# gba-zero.net
KiCad netlist of a schematic drawn in EAGLE
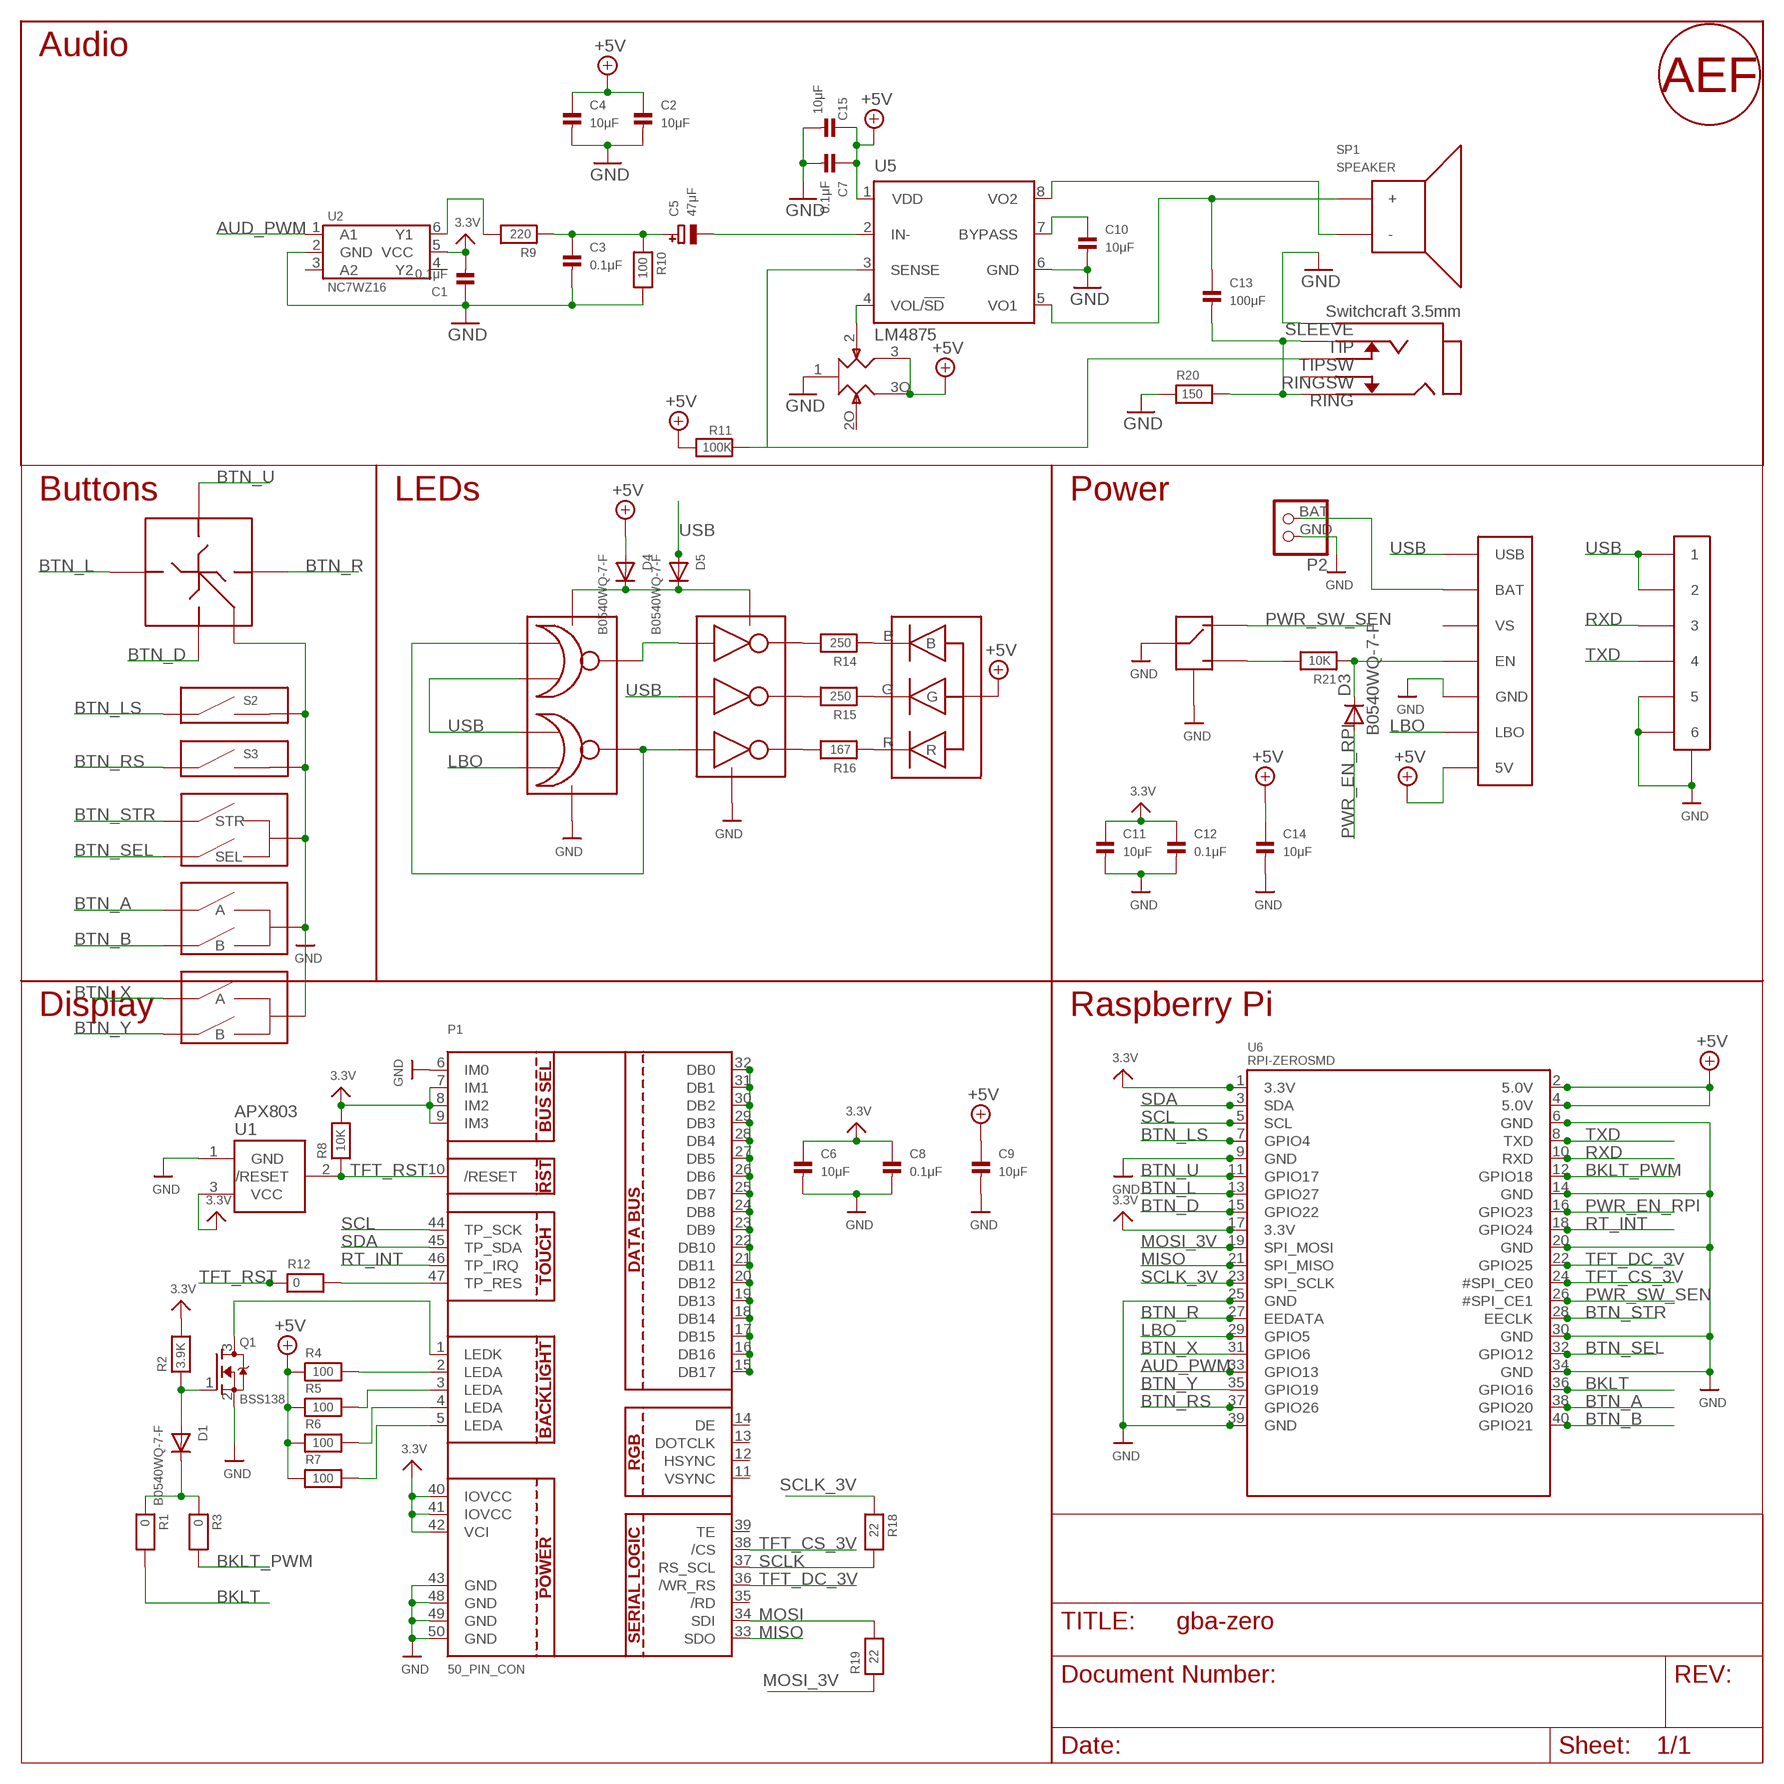
[diagram p0: schematic, sheet 1]

(export (version "E")
  (design (tool "Eeschema 10.0.6"))
  (components
    (comp (ref "C1")
      (value "0.1μF")
      (footprint "eagle-import:0603")
      (libsource (lib "eagle-import") (part "CAP_CERAMIC0603"))
    )
    (comp (ref "C2")
      (value "10μF")
      (footprint "eagle-import:0603")
      (libsource (lib "eagle-import") (part "CAP_CERAMIC0603"))
    )
    (comp (ref "C3")
      (value "0.1μF")
      (footprint "eagle-import:0603")
      (libsource (lib "eagle-import") (part "CAP_CERAMIC0603"))
    )
    (comp (ref "C4")
      (value "10μF")
      (footprint "eagle-import:0603")
      (libsource (lib "eagle-import") (part "CAP_CERAMIC0603"))
    )
    (comp (ref "C5")
      (value "47μF")
      (footprint "eagle-import:EIA6032-28_C-R")
      (libsource (lib "eagle-import") (part "CAP_TANTALUMC/6032_REFLOW"))
    )
    (comp (ref "C6")
      (value "10μF")
      (footprint "eagle-import:0603")
      (libsource (lib "eagle-import") (part "CAP_CERAMIC0603"))
    )
    (comp (ref "C7")
      (value "0.1μF")
      (footprint "eagle-import:0603")
      (libsource (lib "eagle-import") (part "CAP_CERAMIC0603"))
    )
    (comp (ref "C8")
      (value "0.1μF")
      (footprint "eagle-import:0603")
      (libsource (lib "eagle-import") (part "CAP_CERAMIC0603"))
    )
    (comp (ref "C9")
      (value "10μF")
      (footprint "eagle-import:0603")
      (libsource (lib "eagle-import") (part "CAP_CERAMIC0603"))
    )
    (comp (ref "C10")
      (value "10μF")
      (footprint "eagle-import:0603")
      (libsource (lib "eagle-import") (part "CAP_CERAMIC0603"))
    )
    (comp (ref "C11")
      (value "10μF")
      (footprint "eagle-import:0603")
      (libsource (lib "eagle-import") (part "CAP_CERAMIC0603"))
    )
    (comp (ref "C12")
      (value "0.1μF")
      (footprint "eagle-import:0603")
      (libsource (lib "eagle-import") (part "CAP_CERAMIC0603"))
    )
    (comp (ref "C13")
      (value "100μF")
      (footprint "eagle-import:1206")
      (libsource (lib "eagle-import") (part "CAP_CERAMIC1206"))
    )
    (comp (ref "C14")
      (value "10μF")
      (footprint "eagle-import:0603")
      (libsource (lib "eagle-import") (part "CAP_CERAMIC0603"))
    )
    (comp (ref "C15")
      (value "10μF")
      (footprint "eagle-import:0603")
      (libsource (lib "eagle-import") (part "CAP_CERAMIC0603"))
    )
    (comp (ref "D1")
      (value "B0540WQ-7-F")
      (footprint "eagle-import:SOD-123")
      (libsource (lib "eagle-import") (part "DIODESOD-123"))
    )
    (comp (ref "D2")
      (value "LTST-C19HE1WT")
      (footprint "eagle-import:WL-SBCW-0606")
      (libsource (lib "eagle-import") (part "LTST-C19HE1WT"))
    )
    (comp (ref "D3")
      (value "B0540WQ-7-F")
      (footprint "eagle-import:SOD-123")
      (libsource (lib "eagle-import") (part "DIODESOD-123"))
    )
    (comp (ref "D4")
      (value "B0540WQ-7-F")
      (footprint "eagle-import:SOD-123")
      (libsource (lib "eagle-import") (part "DIODESOD-123"))
    )
    (comp (ref "D5")
      (value "B0540WQ-7-F")
      (footprint "eagle-import:SOD-123")
      (libsource (lib "eagle-import") (part "DIODESOD-123"))
    )
    (comp (ref "J1")
      (value "SWTCHCRFT_3.5JACK5-JACK-SMD")
      (footprint "eagle-import:4-JACK-SMD")
      (libsource (lib "eagle-import") (part "SWTCHCRFT_3.5JACK5-JACK-SMD"))
    )
    (comp (ref "P1")
      (value "50_PIN_CON")
      (footprint "eagle-import:FPC-50-CON")
      (libsource (lib "eagle-import") (part "DISP_LCD_CTP28"))
    )
    (comp (ref "P2")
      (value "JST_2PIN")
      (footprint "eagle-import:JSTPH2")
      (libsource (lib "eagle-import") (part "JST_2PIN"))
    )
    (comp (ref "P3")
      (value "LINK_CONNECTOR")
      (footprint "eagle-import:LINK_CONNECTOR")
      (libsource (lib "eagle-import") (part "LINK_CONNECTOR"))
    )
    (comp (ref "Q1")
      (value "BSS138")
      (footprint "eagle-import:SOT23-WIDE")
      (libsource (lib "eagle-import") (part "MOSFET-NWIDE"))
    )
    (comp (ref "R1")
      (value "0")
      (footprint "eagle-import:0603")
      (libsource (lib "eagle-import") (part "RESISTOR0603"))
    )
    (comp (ref "R2")
      (value "3.9K")
      (footprint "eagle-import:0603")
      (libsource (lib "eagle-import") (part "RESISTOR0603"))
    )
    (comp (ref "R3")
      (value "0")
      (footprint "eagle-import:0603")
      (libsource (lib "eagle-import") (part "RESISTOR0603"))
    )
    (comp (ref "R4")
      (value "100")
      (footprint "eagle-import:0603")
      (libsource (lib "eagle-import") (part "RESISTOR0603"))
    )
    (comp (ref "R5")
      (value "100")
      (footprint "eagle-import:0603")
      (libsource (lib "eagle-import") (part "RESISTOR0603"))
    )
    (comp (ref "R6")
      (value "100")
      (footprint "eagle-import:0603")
      (libsource (lib "eagle-import") (part "RESISTOR0603"))
    )
    (comp (ref "R7")
      (value "100")
      (footprint "eagle-import:0603")
      (libsource (lib "eagle-import") (part "RESISTOR0603"))
    )
    (comp (ref "R8")
      (value "10K")
      (footprint "eagle-import:0603")
      (libsource (lib "eagle-import") (part "RESISTOR0603"))
    )
    (comp (ref "R9")
      (value "220")
      (footprint "eagle-import:0603")
      (libsource (lib "eagle-import") (part "RESISTOR0603"))
    )
    (comp (ref "R10")
      (value "100")
      (footprint "eagle-import:0603")
      (libsource (lib "eagle-import") (part "RESISTOR0603"))
    )
    (comp (ref "R11")
      (value "100K")
      (footprint "eagle-import:0603")
      (libsource (lib "eagle-import") (part "RESISTOR0603"))
    )
    (comp (ref "R12")
      (value "0")
      (footprint "eagle-import:0603")
      (libsource (lib "eagle-import") (part "RESISTOR0603"))
    )
    (comp (ref "R14")
      (value "250")
      (footprint "eagle-import:0603")
      (libsource (lib "eagle-import") (part "RESISTOR0603"))
    )
    (comp (ref "R15")
      (value "250")
      (footprint "eagle-import:0603")
      (libsource (lib "eagle-import") (part "RESISTOR0603"))
    )
    (comp (ref "R16")
      (value "167")
      (footprint "eagle-import:0603")
      (libsource (lib "eagle-import") (part "RESISTOR0603"))
    )
    (comp (ref "R17")
      (value "10K")
      (footprint "eagle-import:RK10J12E0A0A")
      (libsource (lib "eagle-import") (part "RK10J12E0A0A"))
    )
    (comp (ref "R18")
      (value "22")
      (footprint "eagle-import:0603")
      (libsource (lib "eagle-import") (part "RESISTOR0603"))
    )
    (comp (ref "R19")
      (value "22")
      (footprint "eagle-import:0603")
      (libsource (lib "eagle-import") (part "RESISTOR0603"))
    )
    (comp (ref "R20")
      (value "150")
      (footprint "eagle-import:0603")
      (libsource (lib "eagle-import") (part "RESISTOR0603"))
    )
    (comp (ref "R21")
      (value "10K")
      (footprint "eagle-import:0603")
      (libsource (lib "eagle-import") (part "RESISTOR0603"))
    )
    (comp (ref "S1")
      (value "D-PAD")
      (footprint "eagle-import:D-PAD")
      (libsource (lib "eagle-import") (part "D-PAD"))
    )
    (comp (ref "S2")
      (value "SHOULDER_BUTTON")
      (footprint "eagle-import:SHOULDER_BUTTON")
      (libsource (lib "eagle-import") (part "SHOULDER_BUTTON"))
    )
    (comp (ref "S3")
      (value "SHOULDER_BUTTON")
      (footprint "eagle-import:SHOULDER_BUTTON")
      (libsource (lib "eagle-import") (part "SHOULDER_BUTTON"))
    )
    (comp (ref "S4")
      (value "START_SELECT_BUTTON")
      (footprint "eagle-import:START_SELECT_BUTTON")
      (libsource (lib "eagle-import") (part "START_SELECT_BUTTON"))
    )
    (comp (ref "S5")
      (value "AB_BUTTON")
      (footprint "eagle-import:AB_BUTTON")
      (libsource (lib "eagle-import") (part "AB_BUTTON"))
    )
    (comp (ref "S6")
      (value "PWR_SWITCH")
      (footprint "eagle-import:PWR-SWITCH")
      (libsource (lib "eagle-import") (part "PWR_SWITCH"))
    )
    (comp (ref "S7")
      (value "AB_BUTTON")
      (footprint "eagle-import:AB_BUTTON")
      (libsource (lib "eagle-import") (part "gbz master_AB_BUTTON"))
    )
    (comp (ref "SP1")
      (value "SPEAKER")
      (footprint "eagle-import:SPEAKER")
      (libsource (lib "eagle-import") (part "SPEAKER"))
    )
    (comp (ref "U$1")
      (value "SIGNATURE")
      (footprint "eagle-import:SIGNATURE")
      (libsource (lib "eagle-import") (part "SIGNATURE"))
    )
    (comp (ref "U1")
      (value "APX803")
      (footprint "eagle-import:SOT23")
      (libsource (lib "eagle-import") (part "AXP083-SAG"))
    )
    (comp (ref "U2")
      (value "NC7WZ16")
      (footprint "eagle-import:SC-70-6")
      (libsource (lib "eagle-import") (part "NC7WZ16"))
    )
    (comp (ref "U3")
      (value "74LVC2G02")
      (footprint "eagle-import:TSSOP-8")
      (libsource (lib "eagle-import") (part "74LVC2G02"))
    )
    (comp (ref "U4")
      (value "74LVC3G04")
      (footprint "eagle-import:TSSOP-8")
      (libsource (lib "eagle-import") (part "74LVC3G04"))
    )
    (comp (ref "U5")
      (value "LM4875")
      (footprint "eagle-import:SO-8")
      (libsource (lib "eagle-import") (part "LM4875"))
    )
    (comp (ref "U6")
      (value "RPI-ZEROSMD")
      (footprint "eagle-import:RPI-SMD")
      (libsource (lib "eagle-import") (part "RPI-ZEROSMD"))
    )
    (comp (ref "U7")
      (value "POWERBOOST-1000C")
      (footprint "eagle-import:POWERBOOST-1000C")
      (libsource (lib "eagle-import") (part "POWERBOOST-1000C"))
    )
  )
  (nets
    (net (code "1") (name "+5V") (class "Default")
      (node (ref "C14") (pin "1") (pinfunction "P$1_1") (pintype "passive"))
      (node (ref "C15") (pin "1") (pinfunction "P$1_1") (pintype "passive"))
      (node (ref "C2") (pin "1") (pinfunction "P$1_1") (pintype "passive"))
      (node (ref "C4") (pin "1") (pinfunction "P$1_1") (pintype "passive"))
      (node (ref "C7") (pin "1") (pinfunction "P$1_1") (pintype "passive"))
      (node (ref "C9") (pin "1") (pinfunction "P$1_1") (pintype "passive"))
      (node (ref "D2") (pin "VCC") (pinfunction "VCC_VCC") (pintype "bidirectional"))
      (node (ref "D4") (pin "A") (pinfunction "A_A") (pintype "passive"))
      (node (ref "R11") (pin "2") (pinfunction "2_2") (pintype "passive"))
      (node (ref "R17") (pin "3") (pinfunction "3_3") (pintype "bidirectional"))
      (node (ref "R17") (pin "3O") (pinfunction "3O_3O") (pintype "bidirectional"))
      (node (ref "R4") (pin "1") (pinfunction "1_1") (pintype "passive"))
      (node (ref "R5") (pin "1") (pinfunction "1_1") (pintype "passive"))
      (node (ref "R6") (pin "1") (pinfunction "1_1") (pintype "passive"))
      (node (ref "R7") (pin "1") (pinfunction "1_1") (pintype "passive"))
      (node (ref "U5") (pin "1") (pinfunction "VDD_1") (pintype "power_in"))
      (node (ref "U6") (pin "2") (pinfunction "5.0V_2") (pintype "bidirectional"))
      (node (ref "U6") (pin "4") (pinfunction "5.0V_4") (pintype "bidirectional"))
      (node (ref "U7") (pin "5V") (pinfunction "5V_5V") (pintype "bidirectional"))
    )
    (net (code "2") (name "/AUD_PWM") (class "Default")
      (node (ref "U2") (pin "1") (pinfunction "A1_1") (pintype "bidirectional"))
      (node (ref "U6") (pin "33") (pinfunction "GPIO13_33") (pintype "bidirectional"))
    )
    (net (code "3") (name "/BKLT") (class "Default")
      (node (ref "R1") (pin "2") (pinfunction "2_2") (pintype "passive"))
      (node (ref "U6") (pin "36") (pinfunction "GPIO16_36") (pintype "bidirectional"))
    )
    (net (code "4") (name "/BKLT_PWM") (class "Default")
      (node (ref "R3") (pin "2") (pinfunction "2_2") (pintype "passive"))
      (node (ref "U6") (pin "12") (pinfunction "GPIO18_12") (pintype "bidirectional"))
    )
    (net (code "5") (name "/BTN_A") (class "Default")
      (node (ref "S5") (pin "A@1") (pinfunction "A_A@1") (pintype "bidirectional"))
      (node (ref "S5") (pin "A@2") (pinfunction "A_A@2") (pintype "bidirectional"))
      (node (ref "U6") (pin "38") (pinfunction "GPIO20_38") (pintype "bidirectional"))
    )
    (net (code "6") (name "/BTN_B") (class "Default")
      (node (ref "S5") (pin "B@1") (pinfunction "B_B@1") (pintype "bidirectional"))
      (node (ref "S5") (pin "B@2") (pinfunction "B_B@2") (pintype "bidirectional"))
      (node (ref "U6") (pin "40") (pinfunction "GPIO21_40") (pintype "bidirectional"))
    )
    (net (code "7") (name "/BTN_D") (class "Default")
      (node (ref "S1") (pin "DOWN") (pinfunction "DOWN_DOWN") (pintype "bidirectional"))
      (node (ref "U6") (pin "15") (pinfunction "GPIO22_15") (pintype "bidirectional"))
    )
    (net (code "8") (name "/BTN_L") (class "Default")
      (node (ref "S1") (pin "LEFT") (pinfunction "LEFT_LEFT") (pintype "bidirectional"))
      (node (ref "U6") (pin "13") (pinfunction "GPIO27_13") (pintype "bidirectional"))
    )
    (net (code "9") (name "/BTN_LS") (class "Default")
      (node (ref "S2") (pin "SW") (pinfunction "1_SW") (pintype "bidirectional"))
      (node (ref "U6") (pin "7") (pinfunction "GPIO4_7") (pintype "bidirectional"))
    )
    (net (code "10") (name "/BTN_R") (class "Default")
      (node (ref "S1") (pin "RIGHT") (pinfunction "RIGHT_RIGHT") (pintype "bidirectional"))
      (node (ref "U6") (pin "27") (pinfunction "EEDATA_27") (pintype "bidirectional"))
    )
    (net (code "11") (name "/BTN_RS") (class "Default")
      (node (ref "S3") (pin "SW") (pinfunction "1_SW") (pintype "bidirectional"))
      (node (ref "U6") (pin "37") (pinfunction "GPIO26_37") (pintype "bidirectional"))
    )
    (net (code "12") (name "/BTN_SEL") (class "Default")
      (node (ref "S4") (pin "SEL") (pinfunction "SEL_SEL") (pintype "bidirectional"))
      (node (ref "U6") (pin "32") (pinfunction "GPIO12_32") (pintype "bidirectional"))
    )
    (net (code "13") (name "/BTN_STR") (class "Default")
      (node (ref "S4") (pin "STR") (pinfunction "STR_STR") (pintype "bidirectional"))
      (node (ref "U6") (pin "28") (pinfunction "EECLK_28") (pintype "bidirectional"))
    )
    (net (code "14") (name "/BTN_U") (class "Default")
      (node (ref "S1") (pin "UP") (pinfunction "UP_UP") (pintype "bidirectional"))
      (node (ref "U6") (pin "11") (pinfunction "GPIO17_11") (pintype "bidirectional"))
    )
    (net (code "15") (name "/BTN_X") (class "Default")
      (node (ref "S7") (pin "A@1") (pinfunction "A_A@1") (pintype "bidirectional"))
      (node (ref "S7") (pin "A@2") (pinfunction "A_A@2") (pintype "bidirectional"))
      (node (ref "U6") (pin "31") (pinfunction "GPIO6_31") (pintype "bidirectional"))
    )
    (net (code "16") (name "/BTN_Y") (class "Default")
      (node (ref "S7") (pin "B@1") (pinfunction "B_B@1") (pintype "bidirectional"))
      (node (ref "S7") (pin "B@2") (pinfunction "B_B@2") (pintype "bidirectional"))
      (node (ref "U6") (pin "35") (pinfunction "GPIO19_35") (pintype "bidirectional"))
    )
    (net (code "17") (name "/LBO") (class "Default")
      (node (ref "U3") (pin "6") (pinfunction "2B_6") (pintype "bidirectional"))
      (node (ref "U6") (pin "29") (pinfunction "GPIO5_29") (pintype "bidirectional"))
      (node (ref "U7") (pin "LBO") (pinfunction "LBO_LBO") (pintype "bidirectional"))
    )
    (net (code "18") (name "/MISO") (class "Default")
      (node (ref "P1") (pin "33") (pinfunction "SDO_33") (pintype "bidirectional"))
      (node (ref "U6") (pin "21") (pinfunction "SPI_MISO_21") (pintype "bidirectional"))
    )
    (net (code "19") (name "/MOSI") (class "Default")
      (node (ref "P1") (pin "34") (pinfunction "SDI_34") (pintype "bidirectional"))
      (node (ref "R19") (pin "2") (pinfunction "2_2") (pintype "passive"))
    )
    (net (code "20") (name "/MOSI_3V") (class "Default")
      (node (ref "R19") (pin "1") (pinfunction "1_1") (pintype "passive"))
      (node (ref "U6") (pin "19") (pinfunction "SPI_MOSI_19") (pintype "bidirectional"))
    )
    (net (code "21") (name "/PWR_EN_RPI") (class "Default")
      (node (ref "D3") (pin "A") (pinfunction "A_A") (pintype "passive"))
      (node (ref "U6") (pin "16") (pinfunction "GPIO23_16") (pintype "bidirectional"))
    )
    (net (code "22") (name "/PWR_SW_SEN") (class "Default")
      (node (ref "S6") (pin "L") (pinfunction "L_L") (pintype "bidirectional"))
      (node (ref "U6") (pin "26") (pinfunction "#SPI_CE1_26") (pintype "bidirectional"))
    )
    (net (code "23") (name "/RT_INT") (class "Default")
      (node (ref "P1") (pin "46") (pinfunction "TP_IRQ_46") (pintype "bidirectional"))
      (node (ref "U6") (pin "18") (pinfunction "GPIO24_18") (pintype "bidirectional"))
    )
    (net (code "24") (name "/RXD") (class "Default")
      (node (ref "P3") (pin "3") (pinfunction "3_3") (pintype "bidirectional"))
      (node (ref "U6") (pin "10") (pinfunction "RXD_10") (pintype "bidirectional"))
    )
    (net (code "25") (name "/SCL") (class "Default")
      (node (ref "P1") (pin "44") (pinfunction "TP_SCK_44") (pintype "bidirectional"))
      (node (ref "U6") (pin "5") (pinfunction "SCL_5") (pintype "bidirectional"))
    )
    (net (code "26") (name "/SCLK") (class "Default")
      (node (ref "P1") (pin "37") (pinfunction "RS_SCL_37") (pintype "bidirectional"))
      (node (ref "R18") (pin "2") (pinfunction "2_2") (pintype "passive"))
    )
    (net (code "27") (name "/SCLK_3V") (class "Default")
      (node (ref "R18") (pin "1") (pinfunction "1_1") (pintype "passive"))
      (node (ref "U6") (pin "23") (pinfunction "SPI_SCLK_23") (pintype "bidirectional"))
    )
    (net (code "28") (name "/SDA") (class "Default")
      (node (ref "P1") (pin "45") (pinfunction "TP_SDA_45") (pintype "bidirectional"))
      (node (ref "U6") (pin "3") (pinfunction "SDA_3") (pintype "bidirectional"))
    )
    (net (code "29") (name "/TFT_CS_3V") (class "Default")
      (node (ref "P1") (pin "38") (pinfunction "/CS_38") (pintype "bidirectional"))
      (node (ref "U6") (pin "24") (pinfunction "#SPI_CE0_24") (pintype "bidirectional"))
    )
    (net (code "30") (name "/TFT_DC_3V") (class "Default")
      (node (ref "P1") (pin "36") (pinfunction "/WR_RS_36") (pintype "bidirectional"))
      (node (ref "U6") (pin "22") (pinfunction "GPIO25_22") (pintype "bidirectional"))
    )
    (net (code "31") (name "/TFT_RST") (class "Default")
      (node (ref "P1") (pin "10") (pinfunction "/RESET_10") (pintype "bidirectional"))
      (node (ref "R12") (pin "1") (pinfunction "1_1") (pintype "passive"))
      (node (ref "R8") (pin "1") (pinfunction "1_1") (pintype "passive"))
      (node (ref "U1") (pin "2") (pinfunction "/RESET_2") (pintype "output"))
    )
    (net (code "32") (name "/TXD") (class "Default")
      (node (ref "P3") (pin "4") (pinfunction "4_4") (pintype "bidirectional"))
      (node (ref "U6") (pin "8") (pinfunction "TXD_8") (pintype "bidirectional"))
    )
    (net (code "33") (name "/USB") (class "Default")
      (node (ref "D5") (pin "A") (pinfunction "A_A") (pintype "passive"))
      (node (ref "P3") (pin "1") (pinfunction "1_1") (pintype "bidirectional"))
      (node (ref "P3") (pin "2") (pinfunction "2_2") (pintype "bidirectional"))
      (node (ref "U3") (pin "2") (pinfunction "1B_2") (pintype "bidirectional"))
      (node (ref "U3") (pin "5") (pinfunction "2A_5") (pintype "bidirectional"))
      (node (ref "U4") (pin "3") (pinfunction "2A_3") (pintype "bidirectional"))
      (node (ref "U7") (pin "USB") (pinfunction "USB_USB") (pintype "bidirectional"))
    )
    (net (code "34") (name "3.3V") (class "Default")
      (node (ref "C1") (pin "2") (pinfunction "P$2_2") (pintype "passive"))
      (node (ref "C11") (pin "1") (pinfunction "P$1_1") (pintype "passive"))
      (node (ref "C12") (pin "1") (pinfunction "P$1_1") (pintype "passive"))
      (node (ref "C6") (pin "1") (pinfunction "P$1_1") (pintype "passive"))
      (node (ref "C8") (pin "1") (pinfunction "P$1_1") (pintype "passive"))
      (node (ref "P1") (pin "40") (pinfunction "IOVCC_40") (pintype "bidirectional"))
      (node (ref "P1") (pin "41") (pinfunction "IOVCC_41") (pintype "bidirectional"))
      (node (ref "P1") (pin "42") (pinfunction "VCI_42") (pintype "bidirectional"))
      (node (ref "P1") (pin "7") (pinfunction "IM1_7") (pintype "bidirectional"))
      (node (ref "P1") (pin "8") (pinfunction "IM2_8") (pintype "bidirectional"))
      (node (ref "P1") (pin "9") (pinfunction "IM3_9") (pintype "bidirectional"))
      (node (ref "R2") (pin "2") (pinfunction "2_2") (pintype "passive"))
      (node (ref "R8") (pin "2") (pinfunction "2_2") (pintype "passive"))
      (node (ref "U1") (pin "3") (pinfunction "VCC_3") (pintype "power_in"))
      (node (ref "U2") (pin "5") (pinfunction "VCC_5") (pintype "bidirectional"))
      (node (ref "U6") (pin "1") (pinfunction "3.3V_1") (pintype "bidirectional"))
      (node (ref "U6") (pin "17") (pinfunction "3.3V_17") (pintype "bidirectional"))
    )
    (net (code "35") (name "GND") (class "Default")
      (node (ref "C1") (pin "1") (pinfunction "P$1_1") (pintype "passive"))
      (node (ref "C10") (pin "2") (pinfunction "P$2_2") (pintype "passive"))
      (node (ref "C11") (pin "2") (pinfunction "P$2_2") (pintype "passive"))
      (node (ref "C12") (pin "2") (pinfunction "P$2_2") (pintype "passive"))
      (node (ref "C14") (pin "2") (pinfunction "P$2_2") (pintype "passive"))
      (node (ref "C15") (pin "2") (pinfunction "P$2_2") (pintype "passive"))
      (node (ref "C2") (pin "2") (pinfunction "P$2_2") (pintype "passive"))
      (node (ref "C3") (pin "2") (pinfunction "P$2_2") (pintype "passive"))
      (node (ref "C4") (pin "2") (pinfunction "P$2_2") (pintype "passive"))
      (node (ref "C6") (pin "2") (pinfunction "P$2_2") (pintype "passive"))
      (node (ref "C7") (pin "2") (pinfunction "P$2_2") (pintype "passive"))
      (node (ref "C8") (pin "2") (pinfunction "P$2_2") (pintype "passive"))
      (node (ref "C9") (pin "2") (pinfunction "P$2_2") (pintype "passive"))
      (node (ref "J1") (pin "1") (pinfunction "1_1") (pintype "bidirectional"))
      (node (ref "P1") (pin "43") (pinfunction "GND_43") (pintype "bidirectional"))
      (node (ref "P1") (pin "48") (pinfunction "GND_48") (pintype "bidirectional"))
      (node (ref "P1") (pin "49") (pinfunction "GND_49") (pintype "bidirectional"))
      (node (ref "P1") (pin "50") (pinfunction "GND_50") (pintype "bidirectional"))
      (node (ref "P1") (pin "6") (pinfunction "IM0_6") (pintype "bidirectional"))
      (node (ref "P2") (pin "GND") (pinfunction "1_GND") (pintype "passive"))
      (node (ref "P3") (pin "5") (pinfunction "5_5") (pintype "bidirectional"))
      (node (ref "P3") (pin "6") (pinfunction "6_6") (pintype "bidirectional"))
      (node (ref "P3") (pin "GND@1") (pinfunction "GND_GND@1") (pintype "bidirectional"))
      (node (ref "P3") (pin "GND@2") (pinfunction "GND_GND@2") (pintype "bidirectional"))
      (node (ref "Q1") (pin "2") (pinfunction "S_2") (pintype "bidirectional"))
      (node (ref "R10") (pin "2") (pinfunction "2_2") (pintype "passive"))
      (node (ref "R17") (pin "1") (pinfunction "1_1") (pintype "bidirectional"))
      (node (ref "R20") (pin "1") (pinfunction "1_1") (pintype "passive"))
      (node (ref "S1") (pin "GND@1") (pinfunction "GND_GND@1") (pintype "bidirectional"))
      (node (ref "S1") (pin "GND@2") (pinfunction "GND_GND@2") (pintype "bidirectional"))
      (node (ref "S1") (pin "GND@3") (pinfunction "GND_GND@3") (pintype "bidirectional"))
      (node (ref "S1") (pin "GND@4") (pinfunction "GND_GND@4") (pintype "bidirectional"))
      (node (ref "S2") (pin "GND@1") (pinfunction "2_GND@1") (pintype "bidirectional"))
      (node (ref "S2") (pin "GND@2") (pinfunction "2_GND@2") (pintype "bidirectional"))
      (node (ref "S2") (pin "GND@3") (pinfunction "2_GND@3") (pintype "bidirectional"))
      (node (ref "S3") (pin "GND@1") (pinfunction "2_GND@1") (pintype "bidirectional"))
      (node (ref "S3") (pin "GND@2") (pinfunction "2_GND@2") (pintype "bidirectional"))
      (node (ref "S3") (pin "GND@3") (pinfunction "2_GND@3") (pintype "bidirectional"))
      (node (ref "S4") (pin "GND@1") (pinfunction "GND_GND@1") (pintype "bidirectional"))
      (node (ref "S4") (pin "GND@2") (pinfunction "GND_GND@2") (pintype "bidirectional"))
      (node (ref "S4") (pin "GND@3") (pinfunction "GND_GND@3") (pintype "bidirectional"))
      (node (ref "S4") (pin "GND@4") (pinfunction "GND_GND@4") (pintype "bidirectional"))
      (node (ref "S5") (pin "GND@1") (pinfunction "GND_GND@1") (pintype "bidirectional"))
      (node (ref "S5") (pin "GND@2") (pinfunction "GND_GND@2") (pintype "bidirectional"))
      (node (ref "S5") (pin "GND@3") (pinfunction "GND_GND@3") (pintype "bidirectional"))
      (node (ref "S5") (pin "GND@4") (pinfunction "GND_GND@4") (pintype "bidirectional"))
      (node (ref "S6") (pin "C@1") (pinfunction "C_C@1") (pintype "bidirectional"))
      (node (ref "S6") (pin "C@2") (pinfunction "C_C@2") (pintype "bidirectional"))
      (node (ref "S6") (pin "GND@1") (pinfunction "GND_GND@1") (pintype "bidirectional"))
      (node (ref "S6") (pin "GND@2") (pinfunction "GND_GND@2") (pintype "bidirectional"))
      (node (ref "S7") (pin "GND@1") (pinfunction "GND_GND@1") (pintype "bidirectional"))
      (node (ref "S7") (pin "GND@2") (pinfunction "GND_GND@2") (pintype "bidirectional"))
      (node (ref "S7") (pin "GND@3") (pinfunction "GND_GND@3") (pintype "bidirectional"))
      (node (ref "S7") (pin "GND@4") (pinfunction "GND_GND@4") (pintype "bidirectional"))
      (node (ref "U1") (pin "1") (pinfunction "GND_1") (pintype "power_in"))
      (node (ref "U2") (pin "2") (pinfunction "GND_2") (pintype "bidirectional"))
      (node (ref "U3") (pin "4") (pinfunction "GND_4") (pintype "bidirectional"))
      (node (ref "U4") (pin "4") (pinfunction "GND_4") (pintype "bidirectional"))
      (node (ref "U5") (pin "6") (pinfunction "GND_6") (pintype "power_in"))
      (node (ref "U6") (pin "14") (pinfunction "GND_14") (pintype "power_in"))
      (node (ref "U6") (pin "20") (pinfunction "GND_20") (pintype "power_in"))
      (node (ref "U6") (pin "25") (pinfunction "GND_25") (pintype "power_in"))
      (node (ref "U6") (pin "30") (pinfunction "GND_30") (pintype "power_in"))
      (node (ref "U6") (pin "34") (pinfunction "GND_34") (pintype "power_in"))
      (node (ref "U6") (pin "39") (pinfunction "GND_39") (pintype "power_in"))
      (node (ref "U6") (pin "6") (pinfunction "GND_6") (pintype "power_in"))
      (node (ref "U6") (pin "9") (pinfunction "GND_9") (pintype "power_in"))
      (node (ref "U7") (pin "GND@1") (pinfunction "GND_GND@1") (pintype "bidirectional"))
      (node (ref "U7") (pin "GND@2") (pinfunction "GND_GND@2") (pintype "bidirectional"))
    )
    (net (code "36") (name "Net-(C3-P$1)") (class "Default")
      (node (ref "C3") (pin "1") (pinfunction "P$1_1") (pintype "passive"))
      (node (ref "C5") (pin "+") (pinfunction "+_+") (pintype "passive"))
      (node (ref "R10") (pin "1") (pinfunction "1_1") (pintype "passive"))
      (node (ref "R9") (pin "1") (pinfunction "1_1") (pintype "passive"))
    )
    (net (code "37") (name "Net-(C10-P$1)") (class "Default")
      (node (ref "C10") (pin "1") (pinfunction "P$1_1") (pintype "passive"))
      (node (ref "U5") (pin "7") (pinfunction "BYPASS_7") (pintype "passive"))
    )
    (net (code "38") (name "Net-(C13-P$1)") (class "Default")
      (node (ref "C13") (pin "1") (pinfunction "P$1_1") (pintype "passive"))
      (node (ref "SP1") (pin "1") (pinfunction "+_1") (pintype "bidirectional"))
      (node (ref "U5") (pin "5") (pinfunction "VO1_5") (pintype "output"))
    )
    (net (code "39") (name "Net-(C13-P$2)") (class "Default")
      (node (ref "C13") (pin "2") (pinfunction "P$2_2") (pintype "passive"))
      (node (ref "J1") (pin "2") (pinfunction "2_2") (pintype "bidirectional"))
      (node (ref "J1") (pin "3") (pinfunction "3_3") (pintype "bidirectional"))
      (node (ref "R20") (pin "2") (pinfunction "2_2") (pintype "passive"))
    )
    (net (code "40") (name "Net-(D1-PadC)") (class "Default")
      (node (ref "D1") (pin "C") (pinfunction "C_C") (pintype "passive"))
      (node (ref "R1") (pin "1") (pinfunction "1_1") (pintype "passive"))
      (node (ref "R3") (pin "1") (pinfunction "1_1") (pintype "passive"))
    )
    (net (code "41") (name "Net-(D2-PadB)") (class "Default")
      (node (ref "D2") (pin "B") (pinfunction "B_B") (pintype "bidirectional"))
      (node (ref "R14") (pin "1") (pinfunction "1_1") (pintype "passive"))
    )
    (net (code "42") (name "Net-(D2-PadG)") (class "Default")
      (node (ref "D2") (pin "G") (pinfunction "G_G") (pintype "bidirectional"))
      (node (ref "R15") (pin "1") (pinfunction "1_1") (pintype "passive"))
    )
    (net (code "43") (name "Net-(D2-PadR)") (class "Default")
      (node (ref "D2") (pin "R") (pinfunction "R_R") (pintype "bidirectional"))
      (node (ref "R16") (pin "1") (pinfunction "1_1") (pintype "passive"))
    )
    (net (code "44") (name "Net-(D3-PadC)") (class "Default")
      (node (ref "D3") (pin "C") (pinfunction "C_C") (pintype "passive"))
      (node (ref "R21") (pin "1") (pinfunction "1_1") (pintype "passive"))
      (node (ref "U7") (pin "EN") (pinfunction "EN_EN") (pintype "bidirectional"))
    )
    (net (code "45") (name "Net-(P1-DB0)") (class "Default")
      (node (ref "P1") (pin "15") (pinfunction "DB17_15") (pintype "bidirectional"))
      (node (ref "P1") (pin "16") (pinfunction "DB16_16") (pintype "bidirectional"))
      (node (ref "P1") (pin "17") (pinfunction "DB15_17") (pintype "bidirectional"))
      (node (ref "P1") (pin "18") (pinfunction "DB14_18") (pintype "bidirectional"))
      (node (ref "P1") (pin "19") (pinfunction "DB13_19") (pintype "bidirectional"))
      (node (ref "P1") (pin "20") (pinfunction "DB12_20") (pintype "bidirectional"))
      (node (ref "P1") (pin "21") (pinfunction "DB11_21") (pintype "bidirectional"))
      (node (ref "P1") (pin "22") (pinfunction "DB10_22") (pintype "bidirectional"))
      (node (ref "P1") (pin "23") (pinfunction "DB9_23") (pintype "bidirectional"))
      (node (ref "P1") (pin "24") (pinfunction "DB8_24") (pintype "bidirectional"))
      (node (ref "P1") (pin "25") (pinfunction "DB7_25") (pintype "bidirectional"))
      (node (ref "P1") (pin "26") (pinfunction "DB6_26") (pintype "bidirectional"))
      (node (ref "P1") (pin "27") (pinfunction "DB5_27") (pintype "bidirectional"))
      (node (ref "P1") (pin "28") (pinfunction "DB4_28") (pintype "bidirectional"))
      (node (ref "P1") (pin "29") (pinfunction "DB3_29") (pintype "bidirectional"))
      (node (ref "P1") (pin "30") (pinfunction "DB2_30") (pintype "bidirectional"))
      (node (ref "P1") (pin "31") (pinfunction "DB1_31") (pintype "bidirectional"))
      (node (ref "P1") (pin "32") (pinfunction "DB0_32") (pintype "bidirectional"))
    )
    (net (code "46") (name "Net-(P1-LEDA-Pad2)") (class "Default")
      (node (ref "P1") (pin "2") (pinfunction "LEDA_2") (pintype "bidirectional"))
      (node (ref "R4") (pin "2") (pinfunction "2_2") (pintype "passive"))
    )
    (net (code "47") (name "Net-(P1-LEDA-Pad3)") (class "Default")
      (node (ref "P1") (pin "3") (pinfunction "LEDA_3") (pintype "bidirectional"))
      (node (ref "R5") (pin "2") (pinfunction "2_2") (pintype "passive"))
    )
    (net (code "48") (name "Net-(P1-LEDA-Pad4)") (class "Default")
      (node (ref "P1") (pin "4") (pinfunction "LEDA_4") (pintype "bidirectional"))
      (node (ref "R6") (pin "2") (pinfunction "2_2") (pintype "passive"))
    )
    (net (code "49") (name "Net-(P1-LEDA-Pad5)") (class "Default")
      (node (ref "P1") (pin "5") (pinfunction "LEDA_5") (pintype "bidirectional"))
      (node (ref "R7") (pin "2") (pinfunction "2_2") (pintype "passive"))
    )
    (net (code "50") (name "Net-(P1-LEDK)") (class "Default")
      (node (ref "P1") (pin "1") (pinfunction "LEDK_1") (pintype "bidirectional"))
      (node (ref "Q1") (pin "3") (pinfunction "D_3") (pintype "bidirectional"))
    )
    (net (code "51") (name "Net-(P1-TP_RES)") (class "Default")
      (node (ref "P1") (pin "47") (pinfunction "TP_RES_47") (pintype "bidirectional"))
      (node (ref "R12") (pin "2") (pinfunction "2_2") (pintype "passive"))
    )
    (net (code "52") (name "Net-(P2-2)") (class "Default")
      (node (ref "P2") (pin "BAT") (pinfunction "2_BAT") (pintype "passive"))
      (node (ref "U7") (pin "BAT") (pinfunction "BAT_BAT") (pintype "bidirectional"))
    )
    (net (code "53") (name "Net-(Q1-G)") (class "Default")
      (node (ref "D1") (pin "A") (pinfunction "A_A") (pintype "passive"))
      (node (ref "Q1") (pin "1") (pinfunction "G_1") (pintype "bidirectional"))
      (node (ref "R2") (pin "1") (pinfunction "1_1") (pintype "passive"))
    )
    (net (code "54") (name "Net-(R21-Pad2)") (class "Default")
      (node (ref "R21") (pin "2") (pinfunction "2_2") (pintype "passive"))
      (node (ref "S6") (pin "R") (pinfunction "R_R") (pintype "bidirectional"))
    )
    (net (code "55") (name "Net-(SP1--)") (class "Default")
      (node (ref "SP1") (pin "2") (pinfunction "-_2") (pintype "bidirectional"))
      (node (ref "U5") (pin "8") (pinfunction "VO2_8") (pintype "output"))
    )
    (net (code "56") (name "Net-(U2-Y1)") (class "Default")
      (node (ref "R9") (pin "2") (pinfunction "2_2") (pintype "passive"))
      (node (ref "U2") (pin "6") (pinfunction "Y1_6") (pintype "bidirectional"))
    )
    (net (code "57") (name "Net-(U3-1A)") (class "Default")
      (node (ref "U3") (pin "1") (pinfunction "1A_1") (pintype "bidirectional"))
      (node (ref "U3") (pin "3") (pinfunction "2Y_3") (pintype "bidirectional"))
      (node (ref "U4") (pin "6") (pinfunction "3A_6") (pintype "bidirectional"))
    )
    (net (code "58") (name "Net-(U3-1Y)") (class "Default")
      (node (ref "U3") (pin "7") (pinfunction "1Y_7") (pintype "bidirectional"))
      (node (ref "U4") (pin "1") (pinfunction "1A_1") (pintype "bidirectional"))
    )
    (net (code "59") (name "Net-(U3-VCC)") (class "Default")
      (node (ref "D4") (pin "C") (pinfunction "C_C") (pintype "passive"))
      (node (ref "D5") (pin "C") (pinfunction "C_C") (pintype "passive"))
      (node (ref "U3") (pin "8") (pinfunction "VCC_8") (pintype "bidirectional"))
      (node (ref "U4") (pin "8") (pinfunction "VCC_8") (pintype "bidirectional"))
    )
    (net (code "60") (name "Net-(U4-1Y)") (class "Default")
      (node (ref "R14") (pin "2") (pinfunction "2_2") (pintype "passive"))
      (node (ref "U4") (pin "7") (pinfunction "1Y_7") (pintype "bidirectional"))
    )
    (net (code "61") (name "Net-(U4-2Y)") (class "Default")
      (node (ref "R15") (pin "2") (pinfunction "2_2") (pintype "passive"))
      (node (ref "U4") (pin "5") (pinfunction "2Y_5") (pintype "bidirectional"))
    )
    (net (code "62") (name "Net-(U4-3Y)") (class "Default")
      (node (ref "R16") (pin "2") (pinfunction "2_2") (pintype "passive"))
      (node (ref "U4") (pin "2") (pinfunction "3Y_2") (pintype "bidirectional"))
    )
    (net (code "63") (name "Net-(U5-IN-)") (class "Default")
      (node (ref "C5") (pin "-") (pinfunction "-_-") (pintype "passive"))
      (node (ref "U5") (pin "2") (pinfunction "IN-_2") (pintype "input"))
    )
    (net (code "64") (name "Net-(U5-SENSE)") (class "Default")
      (node (ref "J1") (pin "5") (pinfunction "5_5") (pintype "bidirectional"))
      (node (ref "R11") (pin "1") (pinfunction "1_1") (pintype "passive"))
      (node (ref "U5") (pin "3") (pinfunction "SENSE_3") (pintype "input"))
    )
    (net (code "65") (name "Net-(U5-VOL{slash}~{SD})") (class "Default")
      (node (ref "R17") (pin "2") (pinfunction "2_2") (pintype "bidirectional"))
      (node (ref "U5") (pin "4") (pinfunction "VOL/~{SD}_4") (pintype "input"))
    )
    (net (code "66") (name "unconnected-(J1-Pad4)") (class "Default")
      (node (ref "J1") (pin "4") (pinfunction "4_4") (pintype "bidirectional"))
    )
    (net (code "67") (name "unconnected-(P1-DE-Pad14)") (class "Default")
      (node (ref "P1") (pin "14") (pinfunction "DE_14") (pintype "bidirectional"))
    )
    (net (code "68") (name "unconnected-(P1-DOTCLK-Pad13)") (class "Default")
      (node (ref "P1") (pin "13") (pinfunction "DOTCLK_13") (pintype "bidirectional"))
    )
    (net (code "69") (name "unconnected-(P1-HSYNC-Pad12)") (class "Default")
      (node (ref "P1") (pin "12") (pinfunction "HSYNC_12") (pintype "bidirectional"))
    )
    (net (code "70") (name "unconnected-(P1-TE-Pad39)") (class "Default")
      (node (ref "P1") (pin "39") (pinfunction "TE_39") (pintype "bidirectional"))
    )
    (net (code "71") (name "unconnected-(P1-VSYNC-Pad11)") (class "Default")
      (node (ref "P1") (pin "11") (pinfunction "VSYNC_11") (pintype "bidirectional"))
    )
    (net (code "72") (name "unconnected-(P1-{slash}RD-Pad35)") (class "Default")
      (node (ref "P1") (pin "35") (pinfunction "/RD_35") (pintype "bidirectional"))
    )
    (net (code "73") (name "unconnected-(R17-Pad2O)") (class "Default")
      (node (ref "R17") (pin "2O") (pinfunction "2O_2O") (pintype "bidirectional"))
    )
    (net (code "74") (name "unconnected-(U2-A2-Pad3)") (class "Default")
      (node (ref "U2") (pin "3") (pinfunction "A2_3") (pintype "bidirectional"))
    )
    (net (code "75") (name "unconnected-(U2-Y2-Pad4)") (class "Default")
      (node (ref "U2") (pin "4") (pinfunction "Y2_4") (pintype "bidirectional"))
    )
    (net (code "76") (name "unconnected-(U7-PadVS)") (class "Default")
      (node (ref "U7") (pin "VS") (pinfunction "VS_VS") (pintype "bidirectional"))
    )
  )
)
